# schematic_esyeda.net
KiCad netlist of a schematic drawn in EasyEDA
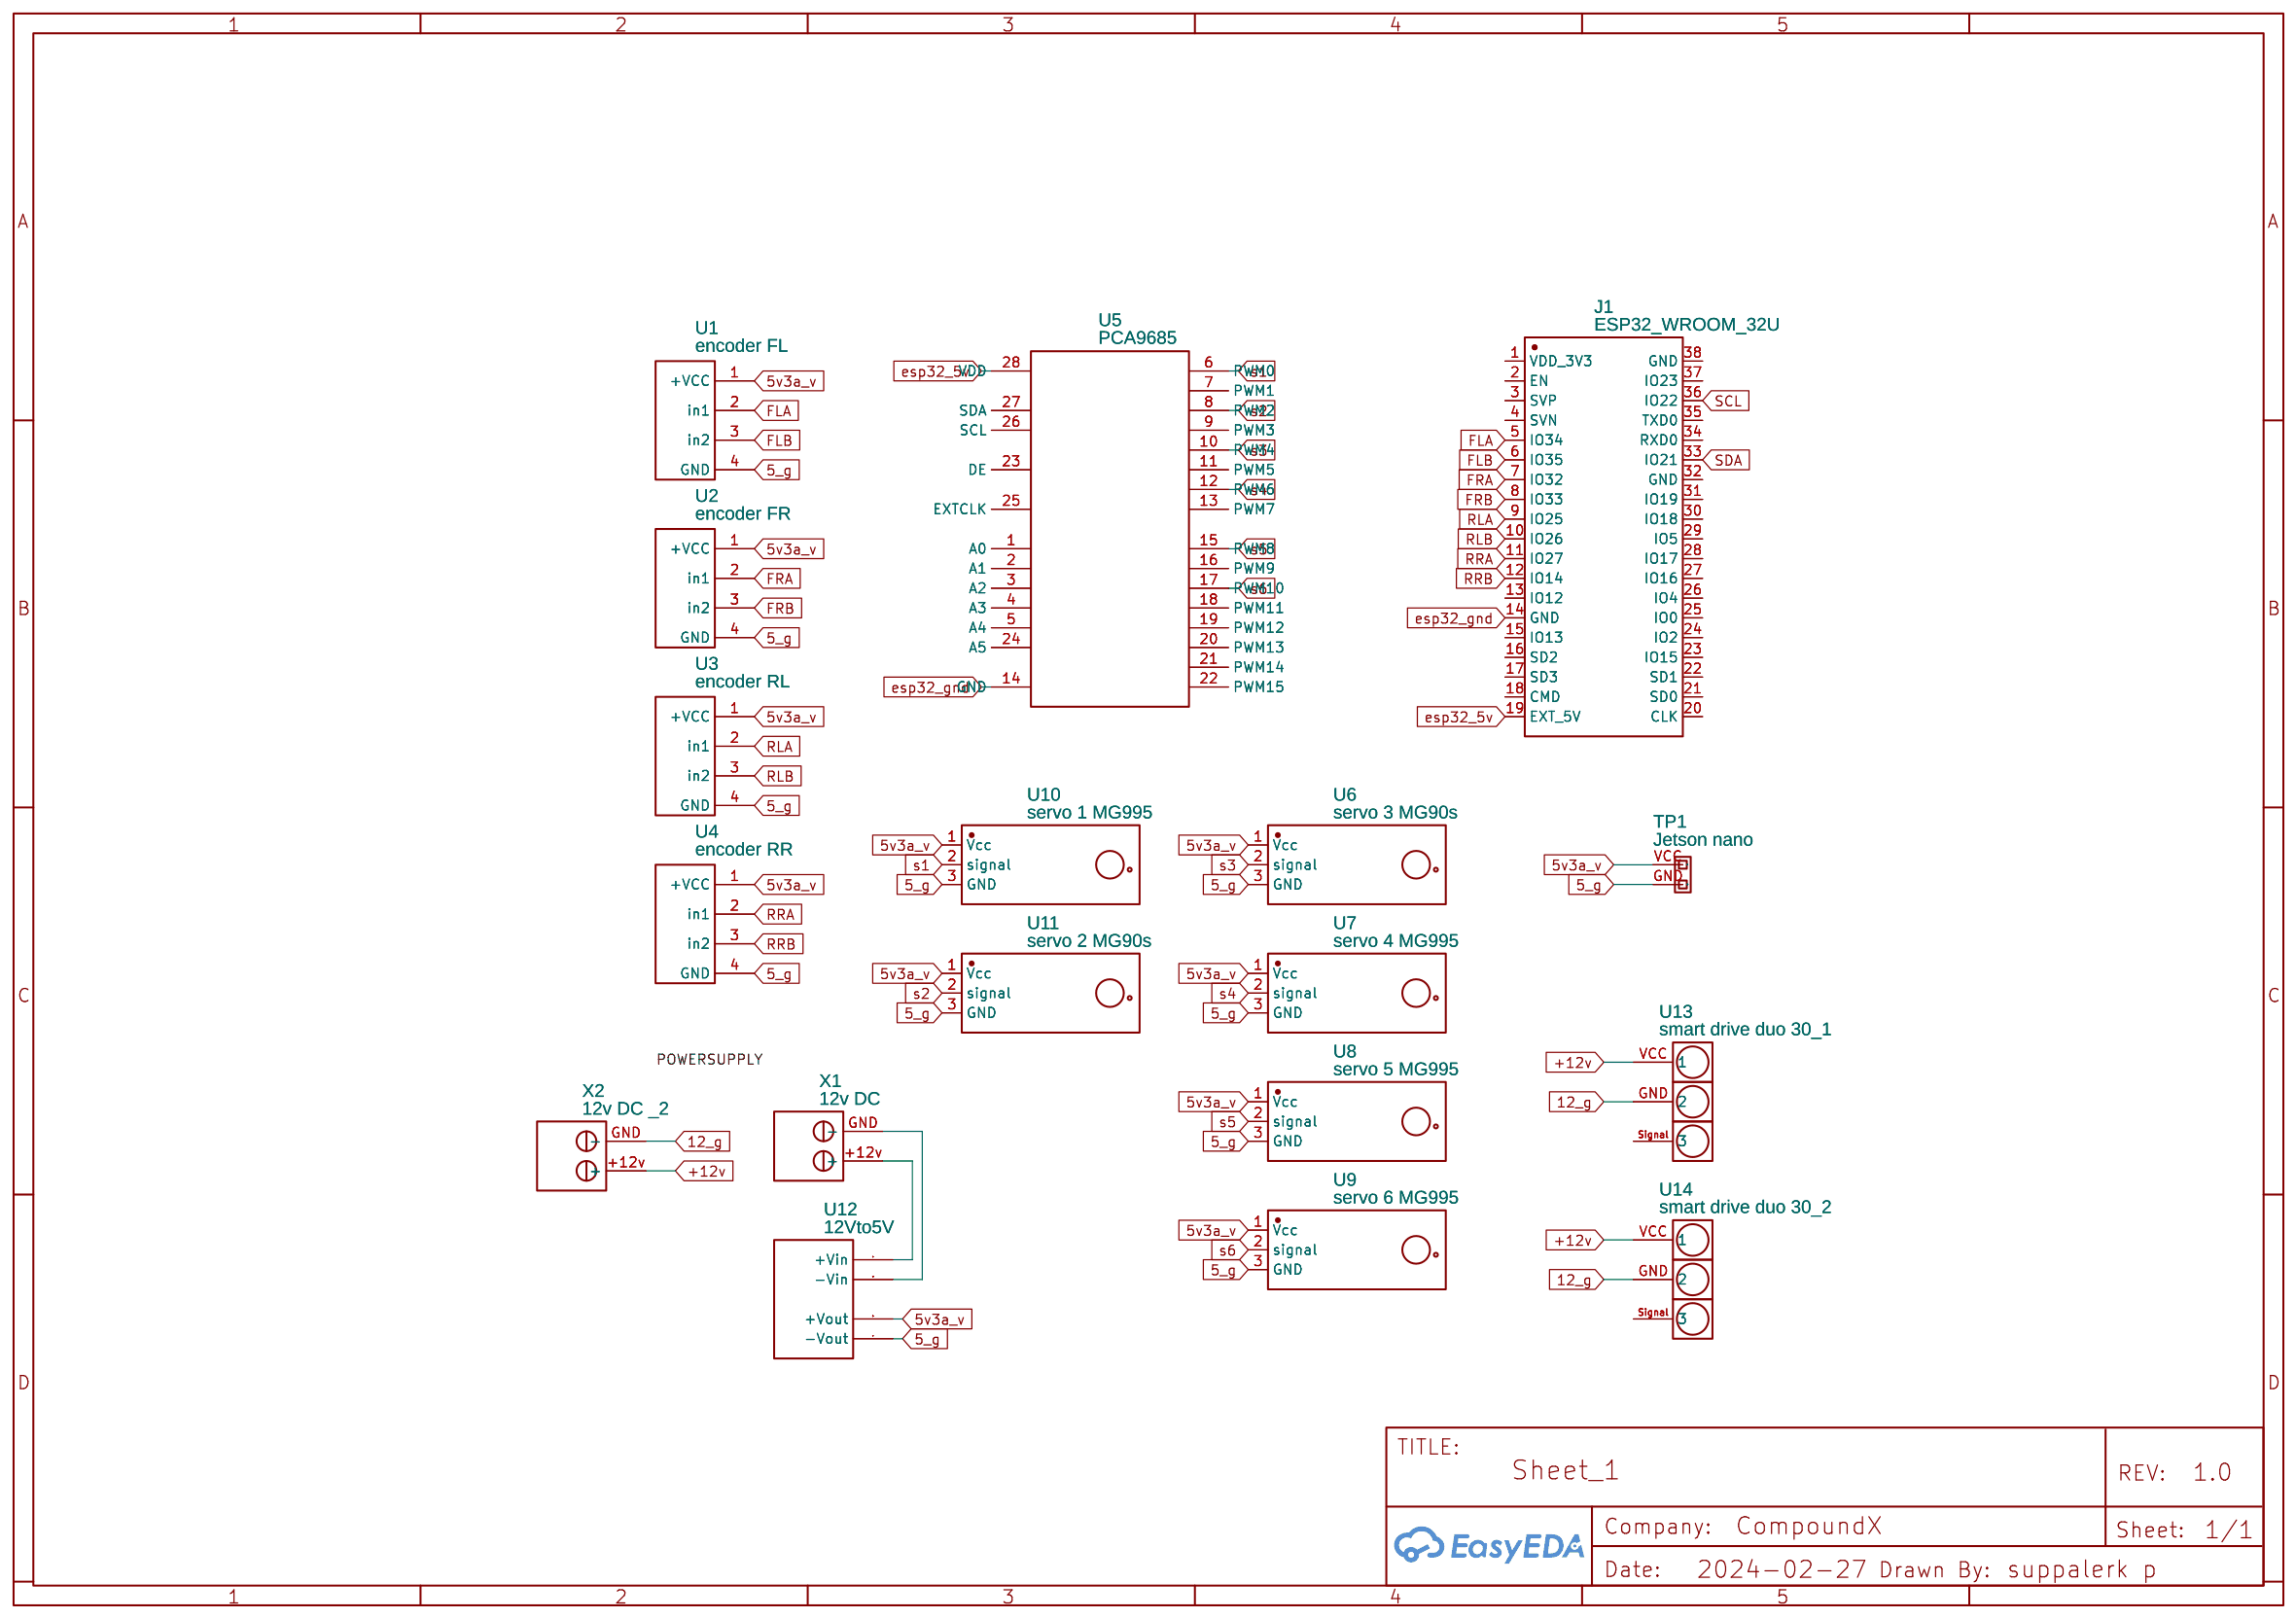
[diagram p0: schematic sheet]

(export (version "E")
  (design (tool "Eeschema 10.0.6"))
  (components
    (comp (ref "J1") (value "ESP32_WROOM_32U") (libsource (lib "") (part "ESP32_WROOM_32U")))
    (comp (ref "TP1") (value "Jetson nano") (libsource (lib "") (part "2PIN")))
    (comp (ref "U1") (value "encoder FL") (libsource (lib "") (part "connector4Pin")))
    (comp (ref "U2") (value "encoder FR") (libsource (lib "") (part "connector4Pin")))
    (comp (ref "U3") (value "encoder RL") (libsource (lib "") (part "connector4Pin")))
    (comp (ref "U4") (value "encoder RR") (libsource (lib "") (part "connector4Pin")))
    (comp (ref "U5")
      (value "PCA9685")
      (fields (field (name "Manufacturer") "NXP Semiconductors"))
      (libsource (lib "") (part "PCA9685"))
    )
    (comp (ref "U6") (value "servo 3 MG90s") (libsource (lib "") (part "MG995")))
    (comp (ref "U7") (value "servo 4 MG995") (libsource (lib "") (part "MG995")))
    (comp (ref "U8") (value "servo 5 MG995") (libsource (lib "") (part "MG995")))
    (comp (ref "U9") (value "servo 6 MG995") (libsource (lib "") (part "MG995")))
    (comp (ref "U10") (value "servo 1 MG995") (libsource (lib "") (part "MG995")))
    (comp (ref "U11") (value "servo 2 MG90s") (libsource (lib "") (part "MG995")))
    (comp (ref "U12") (value "12Vto5V") (libsource (lib "") (part "12Vto5V")))
    (comp (ref "U13") (value "smart drive duo 30_1") (libsource (lib "") (part "10mm_screwterminal_3P")))
    (comp (ref "U14") (value "smart drive duo 30_2") (libsource (lib "") (part "10mm_screwterminal_3P")))
    (comp (ref "X1") (value "12v DC") (libsource (lib "") (part "2PScrewTerminalBlock")))
    (comp (ref "X2") (value "12v DC _2") (libsource (lib "") (part "2PScrewTerminalBlock")))
  )
  (nets
    (net (code "1") (name "+12v") (class "Default")
      (node (ref "U13") (pin "VCC") (pinfunction "1_VCC") (pintype "unspecified"))
      (node (ref "U14") (pin "VCC") (pinfunction "1_VCC") (pintype "unspecified"))
      (node (ref "X2") (pin "+12v") (pinfunction "+_+12v") (pintype "unspecified"))
    )
    (net (code "3") (name "5_g") (class "Default")
      (node (ref "TP1") (pin "GND") (pinfunction "2_GND") (pintype "unspecified"))
      (node (ref "U1") (pin "4") (pinfunction "GND_4") (pintype "unspecified"))
      (node (ref "U10") (pin "3") (pinfunction "GND_3") (pintype "unspecified"))
      (node (ref "U11") (pin "3") (pinfunction "GND_3") (pintype "unspecified"))
      (node (ref "U12") (pin "4") (pinfunction "-Vout_4") (pintype "unspecified"))
      (node (ref "U2") (pin "4") (pinfunction "GND_4") (pintype "unspecified"))
      (node (ref "U3") (pin "4") (pinfunction "GND_4") (pintype "unspecified"))
      (node (ref "U4") (pin "4") (pinfunction "GND_4") (pintype "unspecified"))
      (node (ref "U6") (pin "3") (pinfunction "GND_3") (pintype "unspecified"))
      (node (ref "U7") (pin "3") (pinfunction "GND_3") (pintype "unspecified"))
      (node (ref "U8") (pin "3") (pinfunction "GND_3") (pintype "unspecified"))
      (node (ref "U9") (pin "3") (pinfunction "GND_3") (pintype "unspecified"))
    )
    (net (code "4") (name "5v3a_v") (class "Default")
      (node (ref "TP1") (pin "VCC") (pinfunction "1_VCC") (pintype "unspecified"))
      (node (ref "U1") (pin "1") (pinfunction "+VCC_1") (pintype "unspecified"))
      (node (ref "U10") (pin "1") (pinfunction "Vcc_1") (pintype "unspecified"))
      (node (ref "U11") (pin "1") (pinfunction "Vcc_1") (pintype "unspecified"))
      (node (ref "U12") (pin "3") (pinfunction "+Vout_3") (pintype "unspecified"))
      (node (ref "U2") (pin "1") (pinfunction "+VCC_1") (pintype "unspecified"))
      (node (ref "U3") (pin "1") (pinfunction "+VCC_1") (pintype "unspecified"))
      (node (ref "U4") (pin "1") (pinfunction "+VCC_1") (pintype "unspecified"))
      (node (ref "U6") (pin "1") (pinfunction "Vcc_1") (pintype "unspecified"))
      (node (ref "U7") (pin "1") (pinfunction "Vcc_1") (pintype "unspecified"))
      (node (ref "U8") (pin "1") (pinfunction "Vcc_1") (pintype "unspecified"))
      (node (ref "U9") (pin "1") (pinfunction "Vcc_1") (pintype "unspecified"))
    )
    (net (code "5") (name "12_g") (class "Default")
      (node (ref "U13") (pin "GND") (pinfunction "2_GND") (pintype "unspecified"))
      (node (ref "U14") (pin "GND") (pinfunction "2_GND") (pintype "unspecified"))
      (node (ref "X2") (pin "GND") (pinfunction "-_GND") (pintype "unspecified"))
    )
    (net (code "6") (name "FLA") (class "Default")
      (node (ref "J1") (pin "5") (pinfunction "IO34_5") (pintype "unspecified"))
      (node (ref "U1") (pin "2") (pinfunction "in1_2") (pintype "unspecified"))
    )
    (net (code "7") (name "FLB") (class "Default")
      (node (ref "J1") (pin "6") (pinfunction "IO35_6") (pintype "unspecified"))
      (node (ref "U1") (pin "3") (pinfunction "in2_3") (pintype "unspecified"))
    )
    (net (code "8") (name "FRA") (class "Default")
      (node (ref "J1") (pin "7") (pinfunction "IO32_7") (pintype "unspecified"))
      (node (ref "U2") (pin "2") (pinfunction "in1_2") (pintype "unspecified"))
    )
    (net (code "9") (name "FRB") (class "Default")
      (node (ref "J1") (pin "8") (pinfunction "IO33_8") (pintype "unspecified"))
      (node (ref "U2") (pin "3") (pinfunction "in2_3") (pintype "unspecified"))
    )
    (net (code "10") (name "Net-(U12-+Vin)") (class "Default")
      (node (ref "U12") (pin "1") (pinfunction "+Vin_1") (pintype "unspecified"))
      (node (ref "X1") (pin "+12v") (pinfunction "+_+12v") (pintype "unspecified"))
    )
    (net (code "11") (name "Net-(U12--Vin)") (class "Default")
      (node (ref "U12") (pin "2") (pinfunction "-Vin_2") (pintype "unspecified"))
      (node (ref "X1") (pin "GND") (pinfunction "-_GND") (pintype "unspecified"))
    )
    (net (code "12") (name "RLA") (class "Default")
      (node (ref "J1") (pin "9") (pinfunction "IO25_9") (pintype "unspecified"))
      (node (ref "U3") (pin "2") (pinfunction "in1_2") (pintype "unspecified"))
    )
    (net (code "13") (name "RLB") (class "Default")
      (node (ref "J1") (pin "10") (pinfunction "IO26_10") (pintype "unspecified"))
      (node (ref "U3") (pin "3") (pinfunction "in2_3") (pintype "unspecified"))
    )
    (net (code "14") (name "RRA") (class "Default")
      (node (ref "J1") (pin "11") (pinfunction "IO27_11") (pintype "unspecified"))
      (node (ref "U4") (pin "2") (pinfunction "in1_2") (pintype "unspecified"))
    )
    (net (code "15") (name "RRB") (class "Default")
      (node (ref "J1") (pin "12") (pinfunction "IO14_12") (pintype "unspecified"))
      (node (ref "U4") (pin "3") (pinfunction "in2_3") (pintype "unspecified"))
    )
    (net (code "16") (name "SCL") (class "Default")
      (node (ref "J1") (pin "36") (pinfunction "IO22_36") (pintype "unspecified"))
    )
    (net (code "17") (name "SDA") (class "Default")
      (node (ref "J1") (pin "33") (pinfunction "IO21_33") (pintype "unspecified"))
    )
    (net (code "18") (name "esp32_5v") (class "Default")
      (node (ref "J1") (pin "19") (pinfunction "EXT_5V_19") (pintype "unspecified"))
    )
    (net (code "19") (name "esp32_gnd") (class "Default")
      (node (ref "J1") (pin "14") (pinfunction "GND_14") (pintype "unspecified"))
    )
    (net (code "20") (name "s1") (class "Default")
      (node (ref "U10") (pin "2") (pinfunction "signal_2") (pintype "unspecified"))
    )
    (net (code "21") (name "s2") (class "Default")
      (node (ref "U11") (pin "2") (pinfunction "signal_2") (pintype "unspecified"))
    )
    (net (code "22") (name "s3") (class "Default")
      (node (ref "U6") (pin "2") (pinfunction "signal_2") (pintype "unspecified"))
    )
    (net (code "23") (name "s4") (class "Default")
      (node (ref "U7") (pin "2") (pinfunction "signal_2") (pintype "unspecified"))
    )
    (net (code "24") (name "s5") (class "Default")
      (node (ref "U8") (pin "2") (pinfunction "signal_2") (pintype "unspecified"))
    )
    (net (code "25") (name "s6") (class "Default")
      (node (ref "U9") (pin "2") (pinfunction "signal_2") (pintype "unspecified"))
    )
    (net (code "26") (name "unconnected-(J1-CLK-Pad20)") (class "Default")
      (node (ref "J1") (pin "20") (pinfunction "CLK_20") (pintype "unspecified"))
    )
    (net (code "27") (name "unconnected-(J1-CMD-Pad18)") (class "Default")
      (node (ref "J1") (pin "18") (pinfunction "CMD_18") (pintype "unspecified"))
    )
    (net (code "28") (name "unconnected-(J1-EN-Pad2)") (class "Default")
      (node (ref "J1") (pin "2") (pinfunction "EN_2") (pintype "unspecified"))
    )
    (net (code "29") (name "unconnected-(J1-GND-Pad32)") (class "Default")
      (node (ref "J1") (pin "32") (pinfunction "GND_32") (pintype "unspecified"))
    )
    (net (code "30") (name "unconnected-(J1-GND-Pad38)") (class "Default")
      (node (ref "J1") (pin "38") (pinfunction "GND_38") (pintype "unspecified"))
    )
    (net (code "31") (name "unconnected-(J1-IO0-Pad25)") (class "Default")
      (node (ref "J1") (pin "25") (pinfunction "IO0_25") (pintype "unspecified"))
    )
    (net (code "32") (name "unconnected-(J1-IO2-Pad24)") (class "Default")
      (node (ref "J1") (pin "24") (pinfunction "IO2_24") (pintype "unspecified"))
    )
    (net (code "33") (name "unconnected-(J1-IO4-Pad26)") (class "Default")
      (node (ref "J1") (pin "26") (pinfunction "IO4_26") (pintype "unspecified"))
    )
    (net (code "34") (name "unconnected-(J1-IO5-Pad29)") (class "Default")
      (node (ref "J1") (pin "29") (pinfunction "IO5_29") (pintype "unspecified"))
    )
    (net (code "35") (name "unconnected-(J1-IO12-Pad13)") (class "Default")
      (node (ref "J1") (pin "13") (pinfunction "IO12_13") (pintype "unspecified"))
    )
    (net (code "36") (name "unconnected-(J1-IO13-Pad15)") (class "Default")
      (node (ref "J1") (pin "15") (pinfunction "IO13_15") (pintype "unspecified"))
    )
    (net (code "37") (name "unconnected-(J1-IO15-Pad23)") (class "Default")
      (node (ref "J1") (pin "23") (pinfunction "IO15_23") (pintype "unspecified"))
    )
    (net (code "38") (name "unconnected-(J1-IO16-Pad27)") (class "Default")
      (node (ref "J1") (pin "27") (pinfunction "IO16_27") (pintype "unspecified"))
    )
    (net (code "39") (name "unconnected-(J1-IO17-Pad28)") (class "Default")
      (node (ref "J1") (pin "28") (pinfunction "IO17_28") (pintype "unspecified"))
    )
    (net (code "40") (name "unconnected-(J1-IO18-Pad30)") (class "Default")
      (node (ref "J1") (pin "30") (pinfunction "IO18_30") (pintype "unspecified"))
    )
    (net (code "41") (name "unconnected-(J1-IO19-Pad31)") (class "Default")
      (node (ref "J1") (pin "31") (pinfunction "IO19_31") (pintype "unspecified"))
    )
    (net (code "42") (name "unconnected-(J1-IO23-Pad37)") (class "Default")
      (node (ref "J1") (pin "37") (pinfunction "IO23_37") (pintype "unspecified"))
    )
    (net (code "43") (name "unconnected-(J1-RXD0-Pad34)") (class "Default")
      (node (ref "J1") (pin "34") (pinfunction "RXD0_34") (pintype "unspecified"))
    )
    (net (code "44") (name "unconnected-(J1-SD0-Pad21)") (class "Default")
      (node (ref "J1") (pin "21") (pinfunction "SD0_21") (pintype "unspecified"))
    )
    (net (code "45") (name "unconnected-(J1-SD1-Pad22)") (class "Default")
      (node (ref "J1") (pin "22") (pinfunction "SD1_22") (pintype "unspecified"))
    )
    (net (code "46") (name "unconnected-(J1-SD2-Pad16)") (class "Default")
      (node (ref "J1") (pin "16") (pinfunction "SD2_16") (pintype "unspecified"))
    )
    (net (code "47") (name "unconnected-(J1-SD3-Pad17)") (class "Default")
      (node (ref "J1") (pin "17") (pinfunction "SD3_17") (pintype "unspecified"))
    )
    (net (code "48") (name "unconnected-(J1-SVN-Pad4)") (class "Default")
      (node (ref "J1") (pin "4") (pinfunction "SVN_4") (pintype "unspecified"))
    )
    (net (code "49") (name "unconnected-(J1-SVP-Pad3)") (class "Default")
      (node (ref "J1") (pin "3") (pinfunction "SVP_3") (pintype "unspecified"))
    )
    (net (code "50") (name "unconnected-(J1-TXD0-Pad35)") (class "Default")
      (node (ref "J1") (pin "35") (pinfunction "TXD0_35") (pintype "unspecified"))
    )
    (net (code "51") (name "unconnected-(J1-VDD_3V3-Pad1)") (class "Default")
      (node (ref "J1") (pin "1") (pinfunction "VDD_3V3_1") (pintype "unspecified"))
    )
    (net (code "52") (name "unconnected-(U5-A0-Pad1)") (class "Default")
      (node (ref "U5") (pin "1") (pinfunction "A0_1") (pintype "unspecified"))
    )
    (net (code "53") (name "unconnected-(U5-A1-Pad2)") (class "Default")
      (node (ref "U5") (pin "2") (pinfunction "A1_2") (pintype "unspecified"))
    )
    (net (code "54") (name "unconnected-(U5-A2-Pad3)") (class "Default")
      (node (ref "U5") (pin "3") (pinfunction "A2_3") (pintype "unspecified"))
    )
    (net (code "55") (name "unconnected-(U5-A3-Pad4)") (class "Default")
      (node (ref "U5") (pin "4") (pinfunction "A3_4") (pintype "unspecified"))
    )
    (net (code "56") (name "unconnected-(U5-A4-Pad5)") (class "Default")
      (node (ref "U5") (pin "5") (pinfunction "A4_5") (pintype "unspecified"))
    )
    (net (code "57") (name "unconnected-(U5-A5-Pad24)") (class "Default")
      (node (ref "U5") (pin "24") (pinfunction "A5_24") (pintype "unspecified"))
    )
    (net (code "58") (name "unconnected-(U5-DE-Pad23)") (class "Default")
      (node (ref "U5") (pin "23") (pinfunction "DE_23") (pintype "unspecified"))
    )
    (net (code "59") (name "unconnected-(U5-EXTCLK-Pad25)") (class "Default")
      (node (ref "U5") (pin "25") (pinfunction "EXTCLK_25") (pintype "unspecified"))
    )
    (net (code "60") (name "unconnected-(U5-GND-Pad14)") (class "Default")
      (node (ref "U5") (pin "14") (pinfunction "GND_14") (pintype "unspecified"))
    )
    (net (code "61") (name "unconnected-(U5-PWM0-Pad6)") (class "Default")
      (node (ref "U5") (pin "6") (pinfunction "PWM0_6") (pintype "unspecified"))
    )
    (net (code "62") (name "unconnected-(U5-PWM1-Pad7)") (class "Default")
      (node (ref "U5") (pin "7") (pinfunction "PWM1_7") (pintype "unspecified"))
    )
    (net (code "63") (name "unconnected-(U5-PWM2-Pad8)") (class "Default")
      (node (ref "U5") (pin "8") (pinfunction "PWM2_8") (pintype "unspecified"))
    )
    (net (code "64") (name "unconnected-(U5-PWM3-Pad9)") (class "Default")
      (node (ref "U5") (pin "9") (pinfunction "PWM3_9") (pintype "unspecified"))
    )
    (net (code "65") (name "unconnected-(U5-PWM4-Pad10)") (class "Default")
      (node (ref "U5") (pin "10") (pinfunction "PWM4_10") (pintype "unspecified"))
    )
    (net (code "66") (name "unconnected-(U5-PWM5-Pad11)") (class "Default")
      (node (ref "U5") (pin "11") (pinfunction "PWM5_11") (pintype "unspecified"))
    )
    (net (code "67") (name "unconnected-(U5-PWM6-Pad12)") (class "Default")
      (node (ref "U5") (pin "12") (pinfunction "PWM6_12") (pintype "unspecified"))
    )
    (net (code "68") (name "unconnected-(U5-PWM7-Pad13)") (class "Default")
      (node (ref "U5") (pin "13") (pinfunction "PWM7_13") (pintype "unspecified"))
    )
    (net (code "69") (name "unconnected-(U5-PWM8-Pad15)") (class "Default")
      (node (ref "U5") (pin "15") (pinfunction "PWM8_15") (pintype "unspecified"))
    )
    (net (code "70") (name "unconnected-(U5-PWM9-Pad16)") (class "Default")
      (node (ref "U5") (pin "16") (pinfunction "PWM9_16") (pintype "unspecified"))
    )
    (net (code "71") (name "unconnected-(U5-PWM10-Pad17)") (class "Default")
      (node (ref "U5") (pin "17") (pinfunction "PWM10_17") (pintype "unspecified"))
    )
    (net (code "72") (name "unconnected-(U5-PWM11-Pad18)") (class "Default")
      (node (ref "U5") (pin "18") (pinfunction "PWM11_18") (pintype "unspecified"))
    )
    (net (code "73") (name "unconnected-(U5-PWM12-Pad19)") (class "Default")
      (node (ref "U5") (pin "19") (pinfunction "PWM12_19") (pintype "unspecified"))
    )
    (net (code "74") (name "unconnected-(U5-PWM13-Pad20)") (class "Default")
      (node (ref "U5") (pin "20") (pinfunction "PWM13_20") (pintype "unspecified"))
    )
    (net (code "75") (name "unconnected-(U5-PWM14-Pad21)") (class "Default")
      (node (ref "U5") (pin "21") (pinfunction "PWM14_21") (pintype "unspecified"))
    )
    (net (code "76") (name "unconnected-(U5-PWM15-Pad22)") (class "Default")
      (node (ref "U5") (pin "22") (pinfunction "PWM15_22") (pintype "unspecified"))
    )
    (net (code "77") (name "unconnected-(U5-SCL-Pad26)") (class "Default")
      (node (ref "U5") (pin "26") (pinfunction "SCL_26") (pintype "unspecified"))
    )
    (net (code "78") (name "unconnected-(U5-SDA-Pad27)") (class "Default")
      (node (ref "U5") (pin "27") (pinfunction "SDA_27") (pintype "unspecified"))
    )
    (net (code "79") (name "unconnected-(U5-VDD-Pad28)") (class "Default")
      (node (ref "U5") (pin "28") (pinfunction "VDD_28") (pintype "unspecified"))
    )
    (net (code "80") (name "unconnected-(U13-3-PadSignal)") (class "Default")
      (node (ref "U13") (pin "Signal") (pinfunction "3_Signal") (pintype "unspecified"))
    )
    (net (code "81") (name "unconnected-(U14-3-PadSignal)") (class "Default")
      (node (ref "U14") (pin "Signal") (pinfunction "3_Signal") (pintype "unspecified"))
    )
  )
)
